# MAX17055.net
KiCad netlist of a schematic drawn in Altium Designer
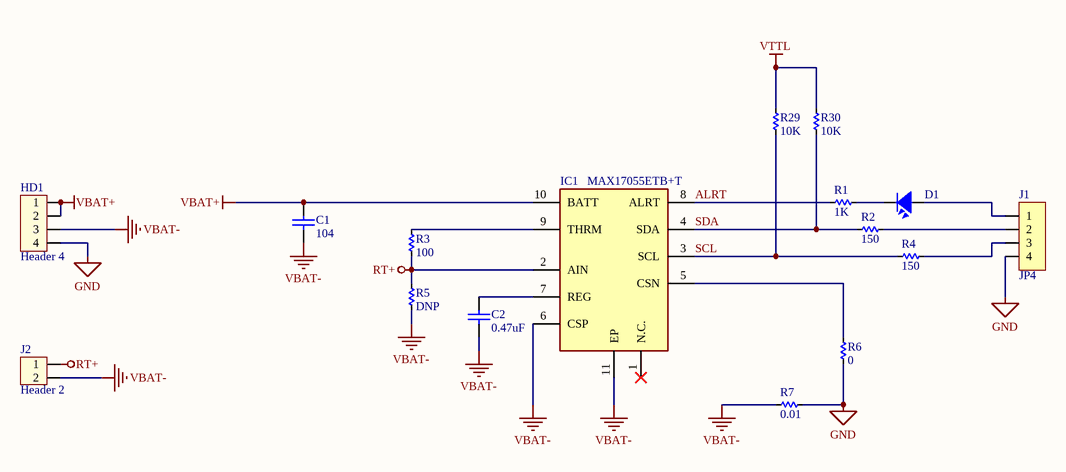
[diagram p0: MAX17055.SchDoc]

(export (version "E")
  (design (tool "Eeschema 10.0.6"))
  (components
    (comp (ref "C1")
      (value "104")
      (footprint "0805 CAP")
      (fields (field (name "PUBLISHER") "Altium Limited"))
      (libsource (lib "ThinhNguyenLib") (part "CAP CERAMIC"))
    )
    (comp (ref "C2")
      (value "0.47uF")
      (footprint "0805 CAP")
      (fields (field (name "PUBLISHER") "Altium Limited"))
      (libsource (lib "ThinhNguyenLib") (part "CAP CERAMIC"))
    )
    (comp (ref "D1") (value "LED") (footprint "LED-0805-Green") (libsource (lib "LIBRARY1") (part "LED SMD")))
    (comp (ref "HD1")
      (value "Header 4")
      (footprint "HED4")
      (description "Header 4 (Green)")
      (libsource (lib "syhaunguyen") (part "Hed4"))
    )
    (comp (ref "IC1")
      (value "MAX17055ETB+T")
      (footprint "SON40P250X200X80-11N")
      (description "Integrated Circuit")
      (fields (field (name "MOUSER PART NUMBER") "700-MAX17055ETB+T"))
      (libsource (lib "SamacSys") (part "MAX17055ETB+T"))
    )
    (comp (ref "J1")
      (value "JP4")
      (footprint "JP4-C1T")
      (description "WR-PHD 2.54 mm Angled Socket Header")
      (fields
        (field (name "MANUFACTURER") "Würth Elektronik eiSos GmbH")
        (field (name "PARTNO") "613004143121")
        (field (name "CREATED BY") "Karrer Zheng")
      )
      (libsource (lib "LIBRARY1") (part "JP4"))
    )
    (comp (ref "J2")
      (value "Header 2")
      (footprint "HED2B")
      (description "Header 2 (Green)")
      (libsource (lib "syhaunguyen") (part "Hed2"))
    )
    (comp (ref "R1")
      (value "1K")
      (footprint "RES-SMD-0805")
      (description "Resistor")
      (fields
        (field (name "MANUFACTURER") "Generic Components")
        (field (name "PUBLISHER") "Altium Hobart Technology Centre")
      )
      (libsource (lib "LIBRARY1") (part "Res-SMD"))
    )
    (comp (ref "R2")
      (value "150")
      (footprint "RES-SMD-0805")
      (description "Resistor")
      (fields
        (field (name "MANUFACTURER") "Generic Components")
        (field (name "PUBLISHER") "Altium Hobart Technology Centre")
      )
      (libsource (lib "LIBRARY1") (part "Res-SMD"))
    )
    (comp (ref "R3")
      (value "100")
      (footprint "RES-SMD-0805")
      (description "Resistor")
      (fields
        (field (name "MANUFACTURER") "Generic Components")
        (field (name "PUBLISHER") "Altium Hobart Technology Centre")
      )
      (libsource (lib "LIBRARY1") (part "Res-SMD"))
    )
    (comp (ref "R4")
      (value "150")
      (footprint "RES-SMD-0805")
      (description "Resistor")
      (fields
        (field (name "MANUFACTURER") "Generic Components")
        (field (name "PUBLISHER") "Altium Hobart Technology Centre")
      )
      (libsource (lib "LIBRARY1") (part "Res-SMD"))
    )
    (comp (ref "R5")
      (value "DNP")
      (footprint "RES-SMD-0805")
      (description "Resistor")
      (fields
        (field (name "MANUFACTURER") "Generic Components")
        (field (name "PUBLISHER") "Altium Hobart Technology Centre")
      )
      (libsource (lib "LIBRARY1") (part "Res-SMD"))
    )
    (comp (ref "R6")
      (value "0")
      (footprint "RES-SMD-0805")
      (description "Resistor")
      (fields
        (field (name "MANUFACTURER") "Generic Components")
        (field (name "PUBLISHER") "Altium Hobart Technology Centre")
      )
      (libsource (lib "LIBRARY1") (part "Res-SMD"))
    )
    (comp (ref "R7")
      (value "0.01")
      (footprint "RES-SMD-0805")
      (description "Resistor")
      (fields
        (field (name "MANUFACTURER") "Generic Components")
        (field (name "PUBLISHER") "Altium Hobart Technology Centre")
      )
      (libsource (lib "LIBRARY1") (part "Res-SMD"))
    )
    (comp (ref "R29")
      (value "10K")
      (footprint "RES-SMD-0805")
      (description "Resistor")
      (fields
        (field (name "MANUFACTURER") "Generic Components")
        (field (name "PUBLISHER") "Altium Hobart Technology Centre")
      )
      (libsource (lib "LIBRARY1") (part "Res-SMD"))
    )
    (comp (ref "R30")
      (value "10K")
      (footprint "RES-SMD-0805")
      (description "Resistor")
      (fields
        (field (name "MANUFACTURER") "Generic Components")
        (field (name "PUBLISHER") "Altium Hobart Technology Centre")
      )
      (libsource (lib "LIBRARY1") (part "Res-SMD"))
    )
  )
  (nets
    (net (code "1") (name "/ALRT") (class "Default")
      (node (ref "IC1") (pin "8") (pinfunction "ALRT_8") (pintype "passive"))
      (node (ref "R1") (pin "1") (pinfunction "1_1") (pintype "passive"))
    )
    (net (code "2") (name "/SCL") (class "Default")
      (node (ref "IC1") (pin "3") (pinfunction "SCL_3") (pintype "passive"))
      (node (ref "R29") (pin "1") (pinfunction "1_1") (pintype "passive"))
      (node (ref "R4") (pin "1") (pinfunction "1_1") (pintype "passive"))
    )
    (net (code "3") (name "/SDA") (class "Default")
      (node (ref "IC1") (pin "4") (pinfunction "SDA_4") (pintype "passive"))
      (node (ref "R2") (pin "1") (pinfunction "1_1") (pintype "passive"))
      (node (ref "R30") (pin "1") (pinfunction "1_1") (pintype "passive"))
    )
    (net (code "4") (name "GND") (class "Default")
      (node (ref "HD1") (pin "4") (pinfunction "4_4") (pintype "passive"))
      (node (ref "J1") (pin "4") (pinfunction "4_4") (pintype "passive"))
      (node (ref "R6") (pin "2") (pinfunction "2_2") (pintype "passive"))
      (node (ref "R7") (pin "1") (pinfunction "1_1") (pintype "passive"))
    )
    (net (code "5") (name "Net-(D1-Pad1)") (class "Default")
      (node (ref "D1") (pin "1") (pinfunction "1_1") (pintype "passive"))
      (node (ref "J1") (pin "1") (pinfunction "1_1") (pintype "passive"))
    )
    (net (code "6") (name "Net-(D1-Pad2)") (class "Default")
      (node (ref "D1") (pin "2") (pinfunction "2_2") (pintype "passive"))
      (node (ref "R1") (pin "2") (pinfunction "2_2") (pintype "passive"))
    )
    (net (code "7") (name "Net-(IC1-CSN)") (class "Default")
      (node (ref "IC1") (pin "5") (pinfunction "CSN_5") (pintype "passive"))
      (node (ref "R6") (pin "1") (pinfunction "1_1") (pintype "passive"))
    )
    (net (code "8") (name "Net-(IC1-REG)") (class "Default")
      (node (ref "C2") (pin "2") (pinfunction "2_2") (pintype "passive"))
      (node (ref "IC1") (pin "7") (pinfunction "REG_7") (pintype "passive"))
    )
    (net (code "9") (name "Net-(IC1-THRM)") (class "Default")
      (node (ref "IC1") (pin "9") (pinfunction "THRM_9") (pintype "passive"))
      (node (ref "R3") (pin "2") (pinfunction "2_2") (pintype "passive"))
    )
    (net (code "10") (name "Net-(J1-Pad2)") (class "Default")
      (node (ref "J1") (pin "2") (pinfunction "2_2") (pintype "passive"))
      (node (ref "R2") (pin "2") (pinfunction "2_2") (pintype "passive"))
    )
    (net (code "11") (name "Net-(J1-Pad3)") (class "Default")
      (node (ref "J1") (pin "3") (pinfunction "3_3") (pintype "passive"))
      (node (ref "R4") (pin "2") (pinfunction "2_2") (pintype "passive"))
    )
    (net (code "12") (name "RT+") (class "Default")
      (node (ref "IC1") (pin "2") (pinfunction "AIN_2") (pintype "passive"))
      (node (ref "J2") (pin "1") (pinfunction "1_1") (pintype "passive"))
      (node (ref "R3") (pin "1") (pinfunction "1_1") (pintype "passive"))
      (node (ref "R5") (pin "2") (pinfunction "2_2") (pintype "passive"))
    )
    (net (code "13") (name "VBAT+") (class "Default")
      (node (ref "C1") (pin "2") (pinfunction "2_2") (pintype "passive"))
      (node (ref "HD1") (pin "1") (pinfunction "1_1") (pintype "passive"))
      (node (ref "HD1") (pin "2") (pinfunction "2_2") (pintype "passive"))
      (node (ref "IC1") (pin "10") (pinfunction "BATT_10") (pintype "passive"))
    )
    (net (code "14") (name "VBAT-") (class "Default")
      (node (ref "C1") (pin "1") (pinfunction "1_1") (pintype "passive"))
      (node (ref "C2") (pin "1") (pinfunction "1_1") (pintype "passive"))
      (node (ref "HD1") (pin "3") (pinfunction "3_3") (pintype "passive"))
      (node (ref "IC1") (pin "11") (pinfunction "EP_11") (pintype "passive"))
      (node (ref "IC1") (pin "6") (pinfunction "CSP_6") (pintype "passive"))
      (node (ref "J2") (pin "2") (pinfunction "2_2") (pintype "passive"))
      (node (ref "R5") (pin "1") (pinfunction "1_1") (pintype "passive"))
      (node (ref "R7") (pin "2") (pinfunction "2_2") (pintype "passive"))
    )
    (net (code "15") (name "VTTL") (class "Default")
      (node (ref "R29") (pin "2") (pinfunction "2_2") (pintype "passive"))
      (node (ref "R30") (pin "2") (pinfunction "2_2") (pintype "passive"))
    )
    (net (code "16") (name "unconnected-(IC1-N.C.-Pad1)") (class "Default")
      (node (ref "IC1") (pin "1") (pinfunction "N.C._1") (pintype "passive+no_connect"))
    )
  )
)
